# HashPower3.net
KiCad netlist of a schematic drawn in Altium Designer
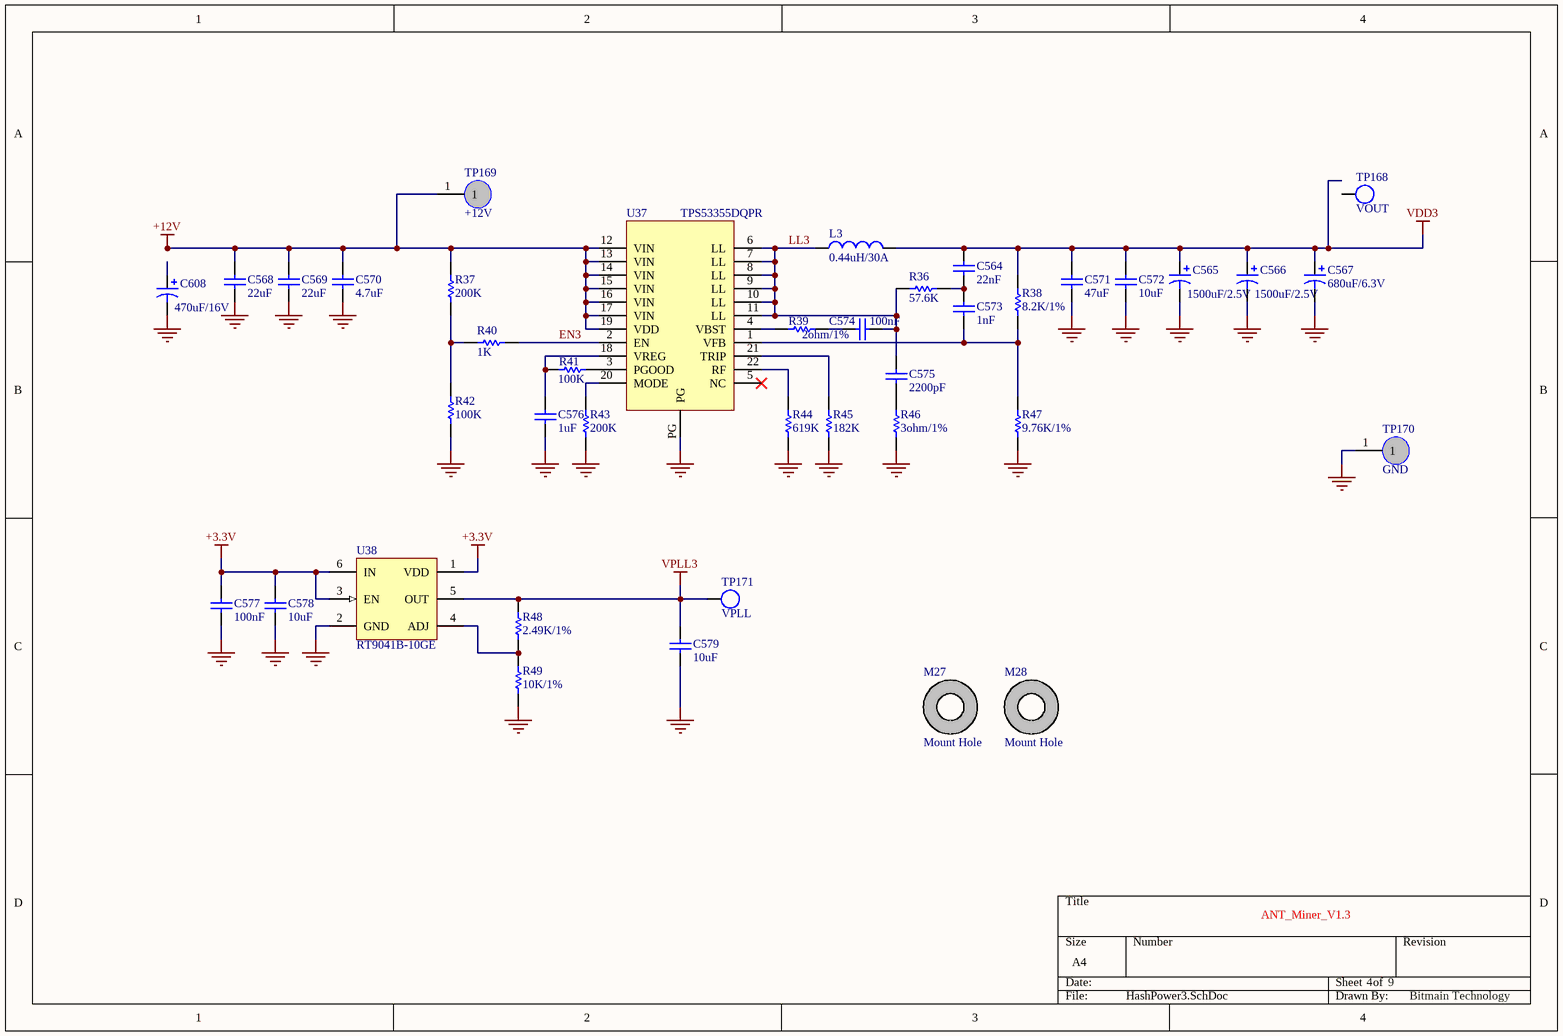
[diagram p0: HashPower3.SchDoc]

(export (version "E")
  (design (tool "Eeschema 10.0.6"))
  (components
    (comp (ref "C564")
      (value "22nF")
      (footprint "CC0603(1608)")
      (description "Capacitor")
      (libsource (lib "ANT_Miner_V1.3") (part "Cap"))
    )
    (comp (ref "C565")
      (value "1500uF/2.5V")
      (footprint "F12")
      (description "Polarized Capacitor (SMD)")
      (fields (field (name "Comment") "1500uF/4V"))
      (libsource (lib "ANT_Miner_V1.3") (part "Cap Pol2"))
    )
    (comp (ref "C566")
      (value "1500uF/2.5V")
      (footprint "F12")
      (description "Polarized Capacitor (SMD)")
      (fields (field (name "Comment") "1500uF/4V"))
      (libsource (lib "ANT_Miner_V1.3") (part "Cap Pol2"))
    )
    (comp (ref "C567")
      (value "680uF/6.3V")
      (footprint "D")
      (description "Polarized Capacitor (Surface Mount)")
      (fields (field (name "PUBLISHER") "Altium Limited"))
      (libsource (lib "Miscellaneous Devices") (part "Cap Pol3"))
    )
    (comp (ref "C568")
      (value "22uF")
      (footprint "CC1210(3225)")
      (description "Capacitor")
      (libsource (lib "ANT_Miner_V1.3") (part "Cap"))
    )
    (comp (ref "C569")
      (value "22uF")
      (footprint "CC1210(3225)")
      (description "Capacitor")
      (libsource (lib "ANT_Miner_V1.3") (part "Cap"))
    )
    (comp (ref "C570")
      (value "4.7uF")
      (footprint "CC0805(2012)")
      (description "Capacitor")
      (libsource (lib "ANT_Miner_V1.3") (part "Cap"))
    )
    (comp (ref "C571")
      (value "47uF")
      (footprint "CAPC3225L")
      (description "Capacitor (Semiconductor SIM Model)")
      (fields (field (name "PUBLISHER") "Altium Limited"))
      (libsource (lib "Miscellaneous Devices") (part "Cap Semi"))
    )
    (comp (ref "C572")
      (value "10uF")
      (footprint "CAPC2012L")
      (description "Capacitor (Semiconductor SIM Model)")
      (fields (field (name "PUBLISHER") "Altium Limited"))
      (libsource (lib "Miscellaneous Devices") (part "Cap Semi"))
    )
    (comp (ref "C573")
      (value "1nF")
      (footprint "CC0603(1608)")
      (description "Capacitor")
      (libsource (lib "ANT_Miner_V1.3") (part "Cap"))
    )
    (comp (ref "C574")
      (value "100nF")
      (footprint "CC0603(1608)")
      (description "Capacitor")
      (libsource (lib "ANT_Miner_V1.3") (part "Cap"))
    )
    (comp (ref "C575")
      (value "2200pF")
      (footprint "CC0603(1608)")
      (description "Capacitor")
      (libsource (lib "ANT_Miner_V1.3") (part "Cap"))
    )
    (comp (ref "C576")
      (value "1uF")
      (footprint "CC0603(1608)")
      (description "Capacitor")
      (libsource (lib "ANT_Miner_V1.3") (part "Cap"))
    )
    (comp (ref "C577")
      (value "100nF")
      (footprint "CC0603(1608)")
      (description "Capacitor (Semiconductor SIM Model)")
      (fields (field (name "PUBLISHER") "Altium Limited"))
      (libsource (lib "CtrlUnit_10U_V1.0") (part "Cap Semi"))
    )
    (comp (ref "C578")
      (value "10uF")
      (footprint "CC0805(2012)")
      (description "Capacitor (Semiconductor SIM Model)")
      (fields (field (name "PUBLISHER") "Altium Limited"))
      (libsource (lib "CtrlUnit_10U_V1.0") (part "Cap Semi"))
    )
    (comp (ref "C579")
      (value "10uF")
      (footprint "CC0805(2012)")
      (description "Capacitor (Semiconductor SIM Model)")
      (fields (field (name "PUBLISHER") "Altium Limited"))
      (libsource (lib "CtrlUnit_10U_V1.0") (part "Cap Semi"))
    )
    (comp (ref "C608")
      (value "470uF/16V")
      (footprint "E12")
      (description "Polarized Capacitor (SMD)")
      (libsource (lib "ANT_Miner_V1.3") (part "Cap Pol2"))
    )
    (comp (ref "L3")
      (value "0.44uH/30A")
      (footprint "IHLP5050")
      (description "Inductor")
      (fields (field (name "PUBLISHER") "Altium Limited"))
      (libsource (lib "Miscellaneous Devices") (part "Inductor"))
    )
    (comp (ref "M27") (value "Mount Hole") (footprint "HOLE_3.2") (libsource (lib "S6_2") (part "M_Hole")))
    (comp (ref "M28") (value "Mount Hole") (footprint "HOLE_3.2") (libsource (lib "S6_2") (part "M_Hole")))
    (comp (ref "R36")
      (value "57.6K")
      (footprint "RR0603(1608)")
      (description "Resistor")
      (libsource (lib "ANT_Miner_V1.3") (part "Res1"))
    )
    (comp (ref "R37")
      (value "200K")
      (footprint "RR0603(1608)")
      (description "Resistor")
      (libsource (lib "ANT_Miner_V1.3") (part "Res1"))
    )
    (comp (ref "R38")
      (value "8.2K/1%")
      (footprint "RR0603(1608)")
      (description "Resistor")
      (libsource (lib "ANT_Miner_V1.3") (part "Res1"))
    )
    (comp (ref "R39")
      (value "2ohm/1%")
      (footprint "RR0603(1608)")
      (description "Resistor")
      (fields (field (name "Comment") "2"))
      (libsource (lib "ANT_Miner_V1.3") (part "Res1"))
    )
    (comp (ref "R40")
      (value "1K")
      (footprint "RR0603(1608)")
      (description "Resistor")
      (libsource (lib "ANT_Miner_V1.3") (part "Res1"))
    )
    (comp (ref "R41")
      (value "100K")
      (footprint "RR0603(1608)")
      (description "Resistor")
      (libsource (lib "ANT_Miner_V1.3") (part "Res1"))
    )
    (comp (ref "R42")
      (value "100K")
      (footprint "RR0603(1608)")
      (description "Resistor")
      (libsource (lib "ANT_Miner_V1.3") (part "Res1"))
    )
    (comp (ref "R43")
      (value "200K")
      (footprint "RR0603(1608)")
      (description "Resistor")
      (libsource (lib "ANT_Miner_V1.3") (part "Res1"))
    )
    (comp (ref "R44")
      (value "619K")
      (footprint "RR0603(1608)")
      (description "Resistor")
      (libsource (lib "ANT_Miner_V1.3") (part "Res1"))
    )
    (comp (ref "R45")
      (value "182K")
      (footprint "RR0603(1608)")
      (description "Resistor")
      (libsource (lib "ANT_Miner_V1.3") (part "Res1"))
    )
    (comp (ref "R46")
      (value "3ohm/1%")
      (footprint "RR0603(1608)")
      (description "Resistor")
      (fields (field (name "Comment") "3"))
      (libsource (lib "ANT_Miner_V1.3") (part "Res1"))
    )
    (comp (ref "R47")
      (value "9.76K/1%")
      (footprint "RR0603(1608)")
      (description "Resistor")
      (libsource (lib "ANT_Miner_V1.3") (part "Res1"))
    )
    (comp (ref "R48")
      (value "2.49K/1%")
      (footprint "RR0603(1608)")
      (description "Resistor")
      (fields (field (name "PUBLISHER") "Altium Limited"))
      (libsource (lib "CtrlUnit_10U_V1.0") (part "Res1"))
    )
    (comp (ref "R49")
      (value "10K/1%")
      (footprint "RR0603(1608)")
      (description "Resistor")
      (fields (field (name "PUBLISHER") "Altium Limited"))
      (libsource (lib "CtrlUnit_10U_V1.0") (part "Res1"))
    )
    (comp (ref "TP168")
      (value "VOUT")
      (footprint "TP_SMD_1.0")
      (description "Test Point")
      (libsource (lib "BitMain_Miner_1") (part "TP"))
    )
    (comp (ref "TP169") (value "+12V") (footprint "TP") (libsource (lib "ANT_Miner_V1.3") (part "TP")))
    (comp (ref "TP170") (value "GND") (footprint "TP") (libsource (lib "ANT_Miner_V1.3") (part "TP")))
    (comp (ref "TP171")
      (value "VPLL")
      (footprint "TP_SMD_1.0")
      (description "Test Point")
      (libsource (lib "BitMain_Miner_1") (part "TP"))
    )
    (comp (ref "U37")
      (value "TPS53355DQPR")
      (footprint "TPS53355")
      (libsource (lib "ANT_Miner_V1.3") (part "TPS53355"))
    )
    (comp (ref "U38")
      (value "RT9041B-10GE")
      (footprint "SOT23-6_L")
      (libsource (lib "USB_Miner") (part "RT9041B-10GE"))
    )
  )
  (nets
    (net (code "1") (name "+3.3V") (class "Default")
      (node (ref "C577") (pin "2") (pinfunction "2_2") (pintype "passive"))
      (node (ref "C578") (pin "2") (pinfunction "2_2") (pintype "passive"))
      (node (ref "U38") (pin "1") (pinfunction "VDD_1") (pintype "power_in"))
      (node (ref "U38") (pin "3") (pinfunction "EN_3") (pintype "input"))
      (node (ref "U38") (pin "6") (pinfunction "IN_6") (pintype "power_in"))
    )
    (net (code "2") (name "+12V") (class "Default")
      (node (ref "C568") (pin "1") (pinfunction "1_1") (pintype "passive"))
      (node (ref "C569") (pin "1") (pinfunction "1_1") (pintype "passive"))
      (node (ref "C570") (pin "1") (pinfunction "1_1") (pintype "passive"))
      (node (ref "R37") (pin "1") (pinfunction "1_1") (pintype "passive"))
      (node (ref "TP169") (pin "1") (pinfunction "1_1") (pintype "passive"))
      (node (ref "U37") (pin "12") (pinfunction "VIN_12") (pintype "passive"))
      (node (ref "U37") (pin "13") (pinfunction "VIN_13") (pintype "passive"))
      (node (ref "U37") (pin "14") (pinfunction "VIN_14") (pintype "passive"))
      (node (ref "U37") (pin "15") (pinfunction "VIN_15") (pintype "passive"))
      (node (ref "U37") (pin "16") (pinfunction "VIN_16") (pintype "passive"))
      (node (ref "U37") (pin "17") (pinfunction "VIN_17") (pintype "passive"))
      (node (ref "U37") (pin "19") (pinfunction "VDD_19") (pintype "passive"))
    )
    (net (code "3") (name "/EN3") (class "Default")
      (node (ref "R40") (pin "2") (pinfunction "2_2") (pintype "passive"))
      (node (ref "U37") (pin "2") (pinfunction "EN_2") (pintype "passive"))
    )
    (net (code "4") (name "/LL3") (class "Default")
      (node (ref "C574") (pin "2") (pinfunction "2_2") (pintype "passive"))
      (node (ref "C575") (pin "1") (pinfunction "1_1") (pintype "passive"))
      (node (ref "L3") (pin "1") (pinfunction "1_1") (pintype "passive"))
      (node (ref "R36") (pin "1") (pinfunction "1_1") (pintype "passive"))
      (node (ref "U37") (pin "10") (pinfunction "LL_10") (pintype "passive"))
      (node (ref "U37") (pin "11") (pinfunction "LL_11") (pintype "passive"))
      (node (ref "U37") (pin "6") (pinfunction "LL_6") (pintype "passive"))
      (node (ref "U37") (pin "7") (pinfunction "LL_7") (pintype "passive"))
      (node (ref "U37") (pin "8") (pinfunction "LL_8") (pintype "passive"))
      (node (ref "U37") (pin "9") (pinfunction "LL_9") (pintype "passive"))
    )
    (net (code "5") (name "GND") (class "Default")
      (node (ref "C565") (pin "2") (pinfunction "2_2") (pintype "passive"))
      (node (ref "C566") (pin "2") (pinfunction "2_2") (pintype "passive"))
      (node (ref "C567") (pin "2") (pinfunction "2_2") (pintype "passive"))
      (node (ref "C568") (pin "2") (pinfunction "2_2") (pintype "passive"))
      (node (ref "C569") (pin "2") (pinfunction "2_2") (pintype "passive"))
      (node (ref "C570") (pin "2") (pinfunction "2_2") (pintype "passive"))
      (node (ref "C571") (pin "1") (pinfunction "1_1") (pintype "passive"))
      (node (ref "C572") (pin "1") (pinfunction "1_1") (pintype "passive"))
      (node (ref "C576") (pin "2") (pinfunction "2_2") (pintype "passive"))
      (node (ref "C577") (pin "1") (pinfunction "1_1") (pintype "passive"))
      (node (ref "C578") (pin "1") (pinfunction "1_1") (pintype "passive"))
      (node (ref "C579") (pin "1") (pinfunction "1_1") (pintype "passive"))
      (node (ref "C608") (pin "2") (pinfunction "2_2") (pintype "passive"))
      (node (ref "R42") (pin "2") (pinfunction "2_2") (pintype "passive"))
      (node (ref "R43") (pin "2") (pinfunction "2_2") (pintype "passive"))
      (node (ref "R44") (pin "2") (pinfunction "2_2") (pintype "passive"))
      (node (ref "R45") (pin "2") (pinfunction "2_2") (pintype "passive"))
      (node (ref "R46") (pin "2") (pinfunction "2_2") (pintype "passive"))
      (node (ref "R47") (pin "2") (pinfunction "2_2") (pintype "passive"))
      (node (ref "R49") (pin "1") (pinfunction "1_1") (pintype "passive"))
      (node (ref "TP170") (pin "1") (pinfunction "1_1") (pintype "passive"))
      (node (ref "U37") (pin "PG") (pinfunction "PG_PG") (pintype "passive"))
      (node (ref "U38") (pin "2") (pinfunction "GND_2") (pintype "power_in"))
    )
    (net (code "6") (name "Net-(C564-Pad2)") (class "Default")
      (node (ref "C564") (pin "2") (pinfunction "2_2") (pintype "passive"))
      (node (ref "C573") (pin "1") (pinfunction "1_1") (pintype "passive"))
      (node (ref "R36") (pin "2") (pinfunction "2_2") (pintype "passive"))
    )
    (net (code "7") (name "Net-(C574-Pad1)") (class "Default")
      (node (ref "C574") (pin "1") (pinfunction "1_1") (pintype "passive"))
      (node (ref "R39") (pin "2") (pinfunction "2_2") (pintype "passive"))
    )
    (net (code "8") (name "Net-(C575-Pad2)") (class "Default")
      (node (ref "C575") (pin "2") (pinfunction "2_2") (pintype "passive"))
      (node (ref "R46") (pin "1") (pinfunction "1_1") (pintype "passive"))
    )
    (net (code "9") (name "Net-(R37-Pad2)") (class "Default")
      (node (ref "R37") (pin "2") (pinfunction "2_2") (pintype "passive"))
      (node (ref "R40") (pin "1") (pinfunction "1_1") (pintype "passive"))
      (node (ref "R42") (pin "1") (pinfunction "1_1") (pintype "passive"))
    )
    (net (code "10") (name "Net-(U37-MODE)") (class "Default")
      (node (ref "R43") (pin "1") (pinfunction "1_1") (pintype "passive"))
      (node (ref "U37") (pin "20") (pinfunction "MODE_20") (pintype "passive"))
    )
    (net (code "11") (name "Net-(U37-PGOOD)") (class "Default")
      (node (ref "R41") (pin "2") (pinfunction "2_2") (pintype "passive"))
      (node (ref "U37") (pin "3") (pinfunction "PGOOD_3") (pintype "passive"))
    )
    (net (code "12") (name "Net-(U37-RF)") (class "Default")
      (node (ref "R44") (pin "1") (pinfunction "1_1") (pintype "passive"))
      (node (ref "U37") (pin "22") (pinfunction "RF_22") (pintype "passive"))
    )
    (net (code "13") (name "Net-(U37-TRIP)") (class "Default")
      (node (ref "R45") (pin "1") (pinfunction "1_1") (pintype "passive"))
      (node (ref "U37") (pin "21") (pinfunction "TRIP_21") (pintype "passive"))
    )
    (net (code "14") (name "Net-(U37-VBST)") (class "Default")
      (node (ref "R39") (pin "1") (pinfunction "1_1") (pintype "passive"))
      (node (ref "U37") (pin "4") (pinfunction "VBST_4") (pintype "passive"))
    )
    (net (code "15") (name "Net-(U37-VFB)") (class "Default")
      (node (ref "C573") (pin "2") (pinfunction "2_2") (pintype "passive"))
      (node (ref "R38") (pin "2") (pinfunction "2_2") (pintype "passive"))
      (node (ref "R47") (pin "1") (pinfunction "1_1") (pintype "passive"))
      (node (ref "U37") (pin "1") (pinfunction "VFB_1") (pintype "passive"))
    )
    (net (code "16") (name "Net-(U37-VREG)") (class "Default")
      (node (ref "C576") (pin "1") (pinfunction "1_1") (pintype "passive"))
      (node (ref "R41") (pin "1") (pinfunction "1_1") (pintype "passive"))
      (node (ref "U37") (pin "18") (pinfunction "VREG_18") (pintype "passive"))
    )
    (net (code "17") (name "Net-(U38-ADJ)") (class "Default")
      (node (ref "R48") (pin "1") (pinfunction "1_1") (pintype "passive"))
      (node (ref "R49") (pin "2") (pinfunction "2_2") (pintype "passive"))
      (node (ref "U38") (pin "4") (pinfunction "ADJ_4") (pintype "passive"))
    )
    (net (code "18") (name "VDD3") (class "Default")
      (node (ref "C564") (pin "1") (pinfunction "1_1") (pintype "passive"))
      (node (ref "C565") (pin "1") (pinfunction "1_1") (pintype "passive"))
      (node (ref "C566") (pin "1") (pinfunction "1_1") (pintype "passive"))
      (node (ref "C567") (pin "1") (pinfunction "1_1") (pintype "passive"))
      (node (ref "C571") (pin "2") (pinfunction "2_2") (pintype "passive"))
      (node (ref "C572") (pin "2") (pinfunction "2_2") (pintype "passive"))
      (node (ref "L3") (pin "2") (pinfunction "2_2") (pintype "passive"))
      (node (ref "R38") (pin "1") (pinfunction "1_1") (pintype "passive"))
    )
    (net (code "19") (name "VPLL3") (class "Default")
      (node (ref "C579") (pin "2") (pinfunction "2_2") (pintype "passive"))
      (node (ref "R48") (pin "2") (pinfunction "2_2") (pintype "passive"))
      (node (ref "TP171") (pin "1") (pinfunction "1_1") (pintype "passive"))
      (node (ref "U38") (pin "5") (pinfunction "OUT_5") (pintype "power_in"))
    )
    (net (code "20") (name "unconnected-(C608-Pad1)") (class "Default")
      (node (ref "C608") (pin "1") (pinfunction "1_1") (pintype "passive"))
    )
    (net (code "21") (name "unconnected-(M27-PIN-Pad0)") (class "Default")
      (node (ref "M27") (pin "0") (pinfunction "PIN_0") (pintype "power_in"))
    )
    (net (code "22") (name "unconnected-(M28-PIN-Pad0)") (class "Default")
      (node (ref "M28") (pin "0") (pinfunction "PIN_0") (pintype "power_in"))
    )
    (net (code "23") (name "unconnected-(TP168-Pad1)") (class "Default")
      (node (ref "TP168") (pin "1") (pinfunction "1_1") (pintype "passive"))
    )
    (net (code "24") (name "unconnected-(U37-NC-Pad5)") (class "Default")
      (node (ref "U37") (pin "5") (pinfunction "NC_5") (pintype "passive+no_connect"))
    )
  )
)
